# RFM69HCW_BOB.net
KiCad netlist of a schematic drawn in Altium Designer
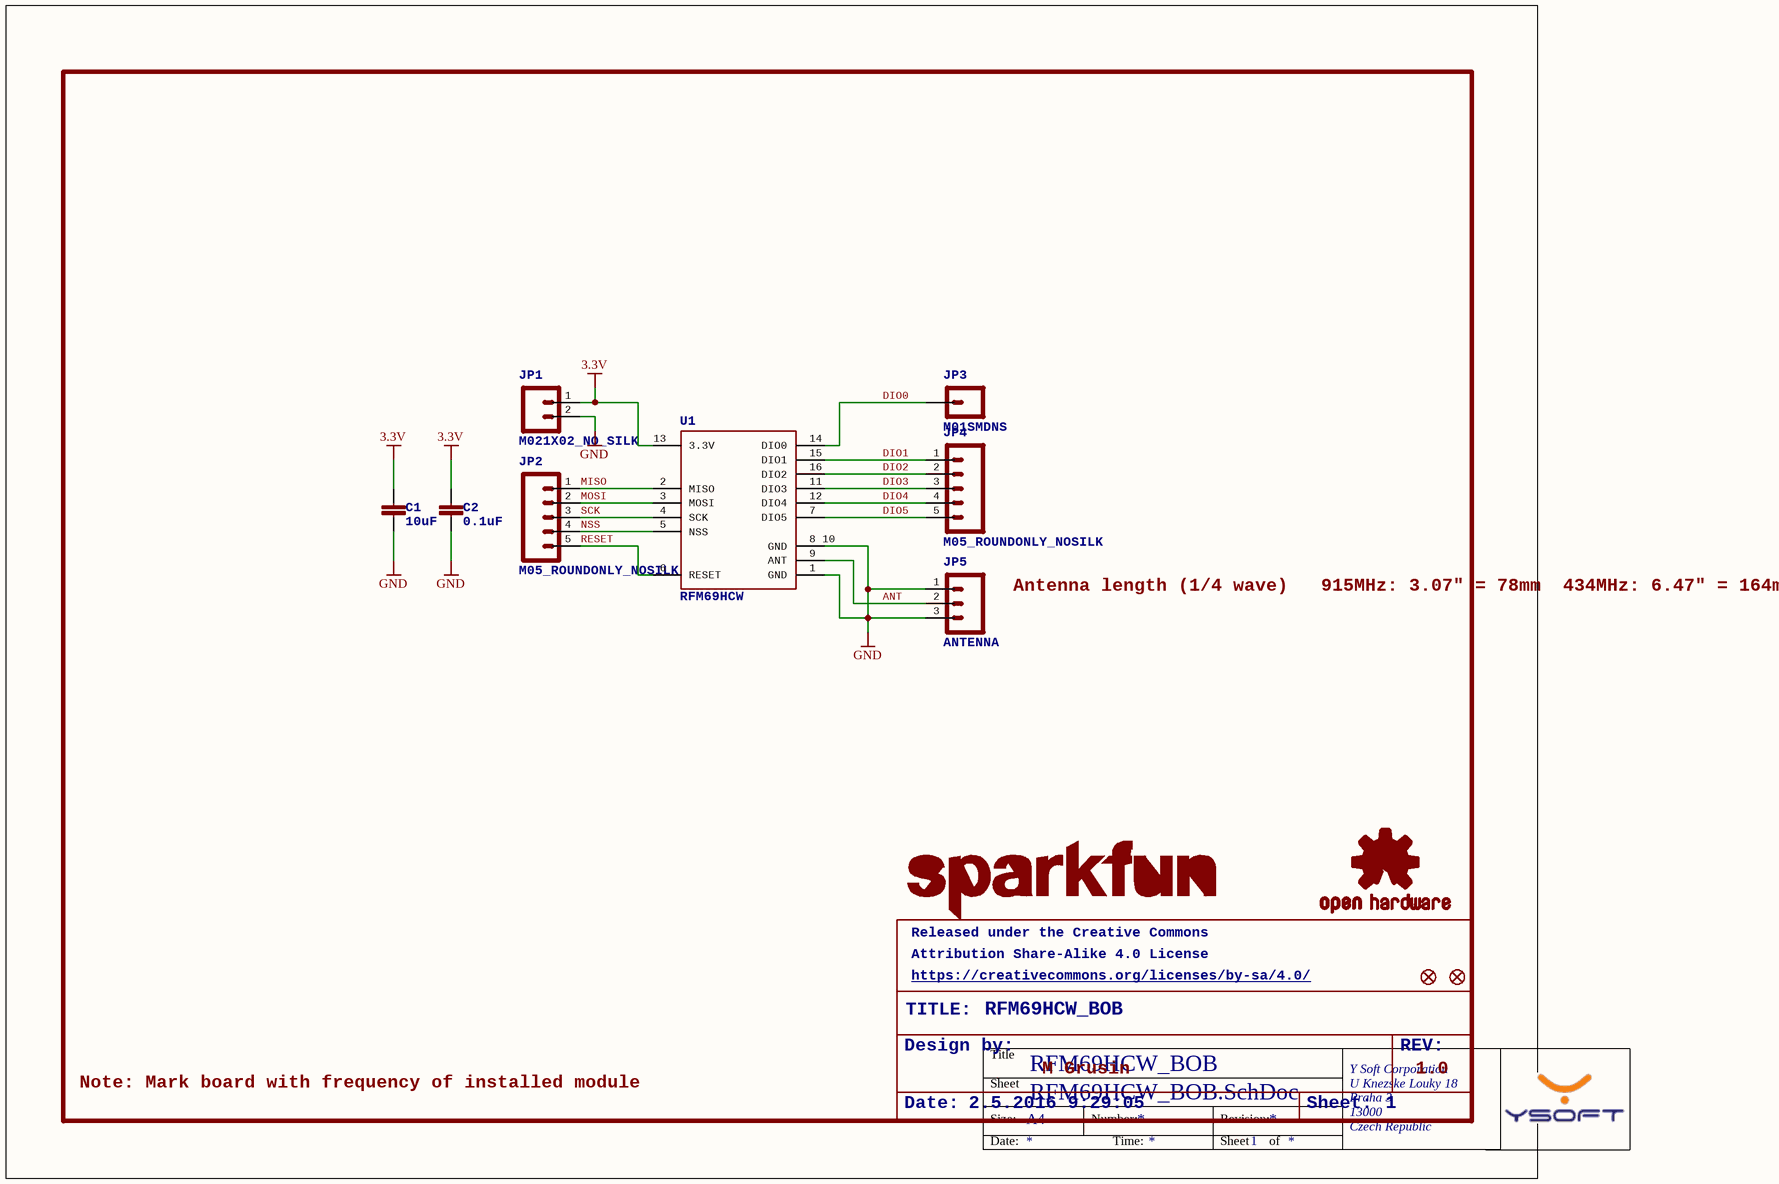
[diagram p0: RFM69HCW_BOB.SchDoc]

(export (version "E")
  (design (tool "Eeschema 10.0.6"))
  (components
    (comp (ref "C1")
      (value "10uF")
      (footprint "1210")
      (description "CAP-09824")
      (libsource (lib "SparkFun-Capacitors") (part "10UF50V20%(1210)"))
    )
    (comp (ref "C2")
      (value "0.1uF")
      (footprint "0603-CAP")
      (description "CAP-00810 Ceramic Standard decoupling cap")
      (libsource (lib "SparkFun-Capacitors") (part "0.1UF-25V(+80/-20%)(0603)"))
    )
    (comp (ref "FID1")
      (value "FIDUCIAL1X2")
      (footprint "FIDUCIAL-1X2")
      (description "Fiducial Alignment PointsVarious fiducial points for machine vision alignment.")
      (libsource (lib "SparkFun-Aesthetics") (part "FIDUCIAL1X2"))
    )
    (comp (ref "FID2")
      (value "FIDUCIAL1X2")
      (footprint "FIDUCIAL-1X2")
      (description "Fiducial Alignment PointsVarious fiducial points for machine vision alignment.")
      (libsource (lib "SparkFun-Aesthetics") (part "FIDUCIAL1X2"))
    )
    (comp (ref "JP1")
      (value "M021X02_NO_SILK")
      (footprint "1X02_NO_SILK")
      (libsource (lib "mike-temp") (part "M021X02_NO_SILK"))
    )
    (comp (ref "JP2")
      (value "M05_ROUNDONLY_NOSILK")
      (footprint "1X05_ROUNDONLY_NOSILK")
      (libsource (lib "mike-temp") (part "M05_ROUNDONLY_NOSILK"))
    )
    (comp (ref "JP3") (value "M01SMDNS") (footprint "1X01NS") (libsource (lib "mike-temp") (part "M01SMDNS")))
    (comp (ref "JP4")
      (value "M05_ROUNDONLY_NOSILK")
      (footprint "1X05_ROUNDONLY_NOSILK")
      (libsource (lib "mike-temp") (part "M05_ROUNDONLY_NOSILK"))
    )
    (comp (ref "JP5")
      (value "ANTENNA")
      (footprint "1X03_ROUND_ONLY_NO_SILK")
      (libsource (lib "mike-temp") (part "M03_ROUND_ONLY_NO_SILK"))
    )
    (comp (ref "LOGO1")
      (value "SFE_LOGO_NAME.1_INCH")
      (footprint "SFE_LOGO_NAME_.1")
      (libsource (lib "SparkFun-Aesthetics") (part "SFE_LOGO_NAME.1_INCH"))
    )
    (comp (ref "LOGO2")
      (value "OSHW-LOGOS")
      (footprint "OSHW-LOGO-S")
      (libsource (lib "SparkFun-Aesthetics") (part "OSHW-LOGOS"))
    )
    (comp (ref "U1")
      (value "RFM69HCW")
      (footprint "RFM69HCW-XXXS2")
      (libsource (lib "mike-temp") (part "RFM69HCW"))
    )
  )
  (nets
    (net (code "1") (name "/ANT") (class "Default")
      (node (ref "JP5") (pin "2") (pinfunction "2_2") (pintype "passive"))
      (node (ref "U1") (pin "9") (pinfunction "ANT_9") (pintype "passive"))
    )
    (net (code "2") (name "/DIO0") (class "Default")
      (node (ref "JP3") (pin "1") (pinfunction "1_1") (pintype "passive"))
      (node (ref "U1") (pin "14") (pinfunction "DIO0_14") (pintype "passive"))
    )
    (net (code "3") (name "/DIO1") (class "Default")
      (node (ref "JP4") (pin "1") (pinfunction "1_1") (pintype "passive"))
      (node (ref "U1") (pin "15") (pinfunction "DIO1_15") (pintype "passive"))
    )
    (net (code "4") (name "/DIO2") (class "Default")
      (node (ref "JP4") (pin "2") (pinfunction "2_2") (pintype "passive"))
      (node (ref "U1") (pin "16") (pinfunction "DIO2_16") (pintype "passive"))
    )
    (net (code "5") (name "/DIO3") (class "Default")
      (node (ref "JP4") (pin "3") (pinfunction "3_3") (pintype "passive"))
      (node (ref "U1") (pin "11") (pinfunction "DIO3_11") (pintype "passive"))
    )
    (net (code "6") (name "/DIO4") (class "Default")
      (node (ref "JP4") (pin "4") (pinfunction "4_4") (pintype "passive"))
      (node (ref "U1") (pin "12") (pinfunction "DIO4_12") (pintype "passive"))
    )
    (net (code "7") (name "/DIO5") (class "Default")
      (node (ref "JP4") (pin "5") (pinfunction "5_5") (pintype "passive"))
      (node (ref "U1") (pin "7") (pinfunction "DIO5_7") (pintype "passive"))
    )
    (net (code "8") (name "/MISO") (class "Default")
      (node (ref "JP2") (pin "1") (pinfunction "1_1") (pintype "passive"))
      (node (ref "U1") (pin "2") (pinfunction "MISO_2") (pintype "passive"))
    )
    (net (code "9") (name "/MOSI") (class "Default")
      (node (ref "JP2") (pin "2") (pinfunction "2_2") (pintype "passive"))
      (node (ref "U1") (pin "3") (pinfunction "MOSI_3") (pintype "passive"))
    )
    (net (code "10") (name "/NSS") (class "Default")
      (node (ref "JP2") (pin "4") (pinfunction "4_4") (pintype "passive"))
      (node (ref "U1") (pin "5") (pinfunction "NSS_5") (pintype "passive"))
    )
    (net (code "11") (name "/RESET") (class "Default")
      (node (ref "JP2") (pin "5") (pinfunction "5_5") (pintype "passive"))
      (node (ref "U1") (pin "6") (pinfunction "RESET_6") (pintype "passive"))
    )
    (net (code "12") (name "/SCK") (class "Default")
      (node (ref "JP2") (pin "3") (pinfunction "3_3") (pintype "passive"))
      (node (ref "U1") (pin "4") (pinfunction "SCK_4") (pintype "passive"))
    )
    (net (code "13") (name "3.3V") (class "Default")
      (node (ref "C1") (pin "1") (pinfunction "1_1") (pintype "passive"))
      (node (ref "C2") (pin "1") (pinfunction "1_1") (pintype "passive"))
      (node (ref "JP1") (pin "1") (pinfunction "1_1") (pintype "passive"))
      (node (ref "U1") (pin "13") (pinfunction "3.3V_13") (pintype "power_in"))
    )
    (net (code "14") (name "GND") (class "Default")
      (node (ref "C1") (pin "2") (pinfunction "2_2") (pintype "passive"))
      (node (ref "C2") (pin "2") (pinfunction "2_2") (pintype "passive"))
      (node (ref "JP1") (pin "2") (pinfunction "2_2") (pintype "passive"))
      (node (ref "JP5") (pin "1") (pinfunction "1_1") (pintype "passive"))
      (node (ref "JP5") (pin "3") (pinfunction "3_3") (pintype "passive"))
      (node (ref "U1") (pin "1") (pinfunction "GND_1") (pintype "power_in"))
      (node (ref "U1") (pin "8_10") (pinfunction "GND_8_10") (pintype "power_in"))
    )
  )
)
